# LEDARRAY.net
KiCad netlist of a schematic drawn in EAGLE
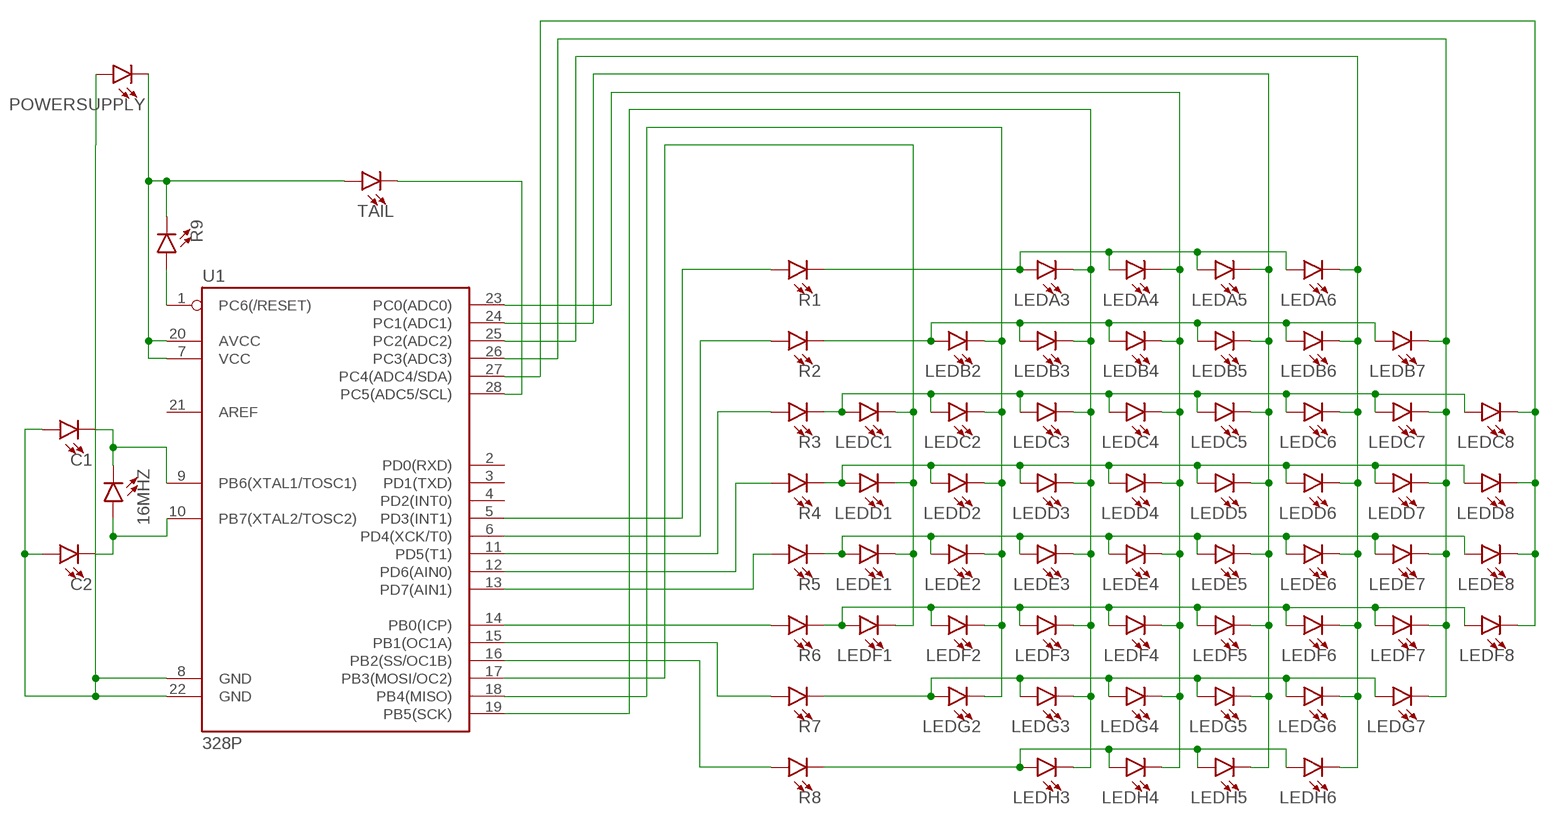
[diagram p0: schematic, sheet 1]

(export (version "E")
  (design (tool "Eeschema 10.0.6"))
  (components
    (comp (ref "16MHZ")
      (value "LED3MM")
      (footprint "eagle-import:LED_3MM")
      (libsource (lib "eagle-import") (part "LED3MM"))
    )
    (comp (ref "C1")
      (value "LED3MM")
      (footprint "eagle-import:LED_3MM")
      (libsource (lib "eagle-import") (part "LED3MM"))
    )
    (comp (ref "C2")
      (value "LED3MM")
      (footprint "eagle-import:LED_3MM")
      (libsource (lib "eagle-import") (part "LED3MM"))
    )
    (comp (ref "LEDA3")
      (value "LED3MM")
      (footprint "eagle-import:LED_3MM")
      (libsource (lib "eagle-import") (part "LED3MM"))
    )
    (comp (ref "LEDA4")
      (value "LED3MM")
      (footprint "eagle-import:LED_3MM")
      (libsource (lib "eagle-import") (part "LED3MM"))
    )
    (comp (ref "LEDA5")
      (value "LED3MM")
      (footprint "eagle-import:LED_3MM")
      (libsource (lib "eagle-import") (part "LED3MM"))
    )
    (comp (ref "LEDA6")
      (value "LED3MM")
      (footprint "eagle-import:LED_3MM")
      (libsource (lib "eagle-import") (part "LED3MM"))
    )
    (comp (ref "LEDB2")
      (value "LED3MM")
      (footprint "eagle-import:LED_3MM")
      (libsource (lib "eagle-import") (part "LED3MM"))
    )
    (comp (ref "LEDB3")
      (value "LED3MM")
      (footprint "eagle-import:LED_3MM")
      (libsource (lib "eagle-import") (part "LED3MM"))
    )
    (comp (ref "LEDB4")
      (value "LED3MM")
      (footprint "eagle-import:LED_3MM")
      (libsource (lib "eagle-import") (part "LED3MM"))
    )
    (comp (ref "LEDB5")
      (value "LED3MM")
      (footprint "eagle-import:LED_3MM")
      (libsource (lib "eagle-import") (part "LED3MM"))
    )
    (comp (ref "LEDB6")
      (value "LED3MM")
      (footprint "eagle-import:LED_3MM")
      (libsource (lib "eagle-import") (part "LED3MM"))
    )
    (comp (ref "LEDB7")
      (value "LED3MM")
      (footprint "eagle-import:LED_3MM")
      (libsource (lib "eagle-import") (part "LED3MM"))
    )
    (comp (ref "LEDC1")
      (value "LED3MM")
      (footprint "eagle-import:LED_3MM")
      (libsource (lib "eagle-import") (part "LED3MM"))
    )
    (comp (ref "LEDC2")
      (value "LED3MM")
      (footprint "eagle-import:LED_3MM")
      (libsource (lib "eagle-import") (part "LED3MM"))
    )
    (comp (ref "LEDC3")
      (value "LED3MM")
      (footprint "eagle-import:LED_3MM")
      (libsource (lib "eagle-import") (part "LED3MM"))
    )
    (comp (ref "LEDC4")
      (value "LED3MM")
      (footprint "eagle-import:LED_3MM")
      (libsource (lib "eagle-import") (part "LED3MM"))
    )
    (comp (ref "LEDC5")
      (value "LED3MM")
      (footprint "eagle-import:LED_3MM")
      (libsource (lib "eagle-import") (part "LED3MM"))
    )
    (comp (ref "LEDC6")
      (value "LED3MM")
      (footprint "eagle-import:LED_3MM")
      (libsource (lib "eagle-import") (part "LED3MM"))
    )
    (comp (ref "LEDC7")
      (value "LED3MM")
      (footprint "eagle-import:LED_3MM")
      (libsource (lib "eagle-import") (part "LED3MM"))
    )
    (comp (ref "LEDC8")
      (value "LED3MM")
      (footprint "eagle-import:LED_3MM")
      (libsource (lib "eagle-import") (part "LED3MM"))
    )
    (comp (ref "LEDD1")
      (value "LED3MM")
      (footprint "eagle-import:LED_3MM")
      (libsource (lib "eagle-import") (part "LED3MM"))
    )
    (comp (ref "LEDD2")
      (value "LED3MM")
      (footprint "eagle-import:LED_3MM")
      (libsource (lib "eagle-import") (part "LED3MM"))
    )
    (comp (ref "LEDD3")
      (value "LED3MM")
      (footprint "eagle-import:LED_3MM")
      (libsource (lib "eagle-import") (part "LED3MM"))
    )
    (comp (ref "LEDD4")
      (value "LED3MM")
      (footprint "eagle-import:LED_3MM")
      (libsource (lib "eagle-import") (part "LED3MM"))
    )
    (comp (ref "LEDD5")
      (value "LED3MM")
      (footprint "eagle-import:LED_3MM")
      (libsource (lib "eagle-import") (part "LED3MM"))
    )
    (comp (ref "LEDD6")
      (value "LED3MM")
      (footprint "eagle-import:LED_3MM")
      (libsource (lib "eagle-import") (part "LED3MM"))
    )
    (comp (ref "LEDD7")
      (value "LED3MM")
      (footprint "eagle-import:LED_3MM")
      (libsource (lib "eagle-import") (part "LED3MM"))
    )
    (comp (ref "LEDD8")
      (value "LED3MM")
      (footprint "eagle-import:LED_3MM")
      (libsource (lib "eagle-import") (part "LED3MM"))
    )
    (comp (ref "LEDE1")
      (value "LED3MM")
      (footprint "eagle-import:LED_3MM")
      (libsource (lib "eagle-import") (part "LED3MM"))
    )
    (comp (ref "LEDE2")
      (value "LED3MM")
      (footprint "eagle-import:LED_3MM")
      (libsource (lib "eagle-import") (part "LED3MM"))
    )
    (comp (ref "LEDE3")
      (value "LED3MM")
      (footprint "eagle-import:LED_3MM")
      (libsource (lib "eagle-import") (part "LED3MM"))
    )
    (comp (ref "LEDE4")
      (value "LED3MM")
      (footprint "eagle-import:LED_3MM")
      (libsource (lib "eagle-import") (part "LED3MM"))
    )
    (comp (ref "LEDE5")
      (value "LED3MM")
      (footprint "eagle-import:LED_3MM")
      (libsource (lib "eagle-import") (part "LED3MM"))
    )
    (comp (ref "LEDE6")
      (value "LED3MM")
      (footprint "eagle-import:LED_3MM")
      (libsource (lib "eagle-import") (part "LED3MM"))
    )
    (comp (ref "LEDE7")
      (value "LED3MM")
      (footprint "eagle-import:LED_3MM")
      (libsource (lib "eagle-import") (part "LED3MM"))
    )
    (comp (ref "LEDE8")
      (value "LED3MM")
      (footprint "eagle-import:LED_3MM")
      (libsource (lib "eagle-import") (part "LED3MM"))
    )
    (comp (ref "LEDF1")
      (value "LED3MM")
      (footprint "eagle-import:LED_3MM")
      (libsource (lib "eagle-import") (part "LED3MM"))
    )
    (comp (ref "LEDF2")
      (value "LED3MM")
      (footprint "eagle-import:LED_3MM")
      (libsource (lib "eagle-import") (part "LED3MM"))
    )
    (comp (ref "LEDF3")
      (value "LED3MM")
      (footprint "eagle-import:LED_3MM")
      (libsource (lib "eagle-import") (part "LED3MM"))
    )
    (comp (ref "LEDF4")
      (value "LED3MM")
      (footprint "eagle-import:LED_3MM")
      (libsource (lib "eagle-import") (part "LED3MM"))
    )
    (comp (ref "LEDF5")
      (value "LED3MM")
      (footprint "eagle-import:LED_3MM")
      (libsource (lib "eagle-import") (part "LED3MM"))
    )
    (comp (ref "LEDF6")
      (value "LED3MM")
      (footprint "eagle-import:LED_3MM")
      (libsource (lib "eagle-import") (part "LED3MM"))
    )
    (comp (ref "LEDF7")
      (value "LED3MM")
      (footprint "eagle-import:LED_3MM")
      (libsource (lib "eagle-import") (part "LED3MM"))
    )
    (comp (ref "LEDF8")
      (value "LED3MM")
      (footprint "eagle-import:LED_3MM")
      (libsource (lib "eagle-import") (part "LED3MM"))
    )
    (comp (ref "LEDG2")
      (value "LED3MM")
      (footprint "eagle-import:LED_3MM")
      (libsource (lib "eagle-import") (part "LED3MM"))
    )
    (comp (ref "LEDG3")
      (value "LED3MM")
      (footprint "eagle-import:LED_3MM")
      (libsource (lib "eagle-import") (part "LED3MM"))
    )
    (comp (ref "LEDG4")
      (value "LED3MM")
      (footprint "eagle-import:LED_3MM")
      (libsource (lib "eagle-import") (part "LED3MM"))
    )
    (comp (ref "LEDG5")
      (value "LED3MM")
      (footprint "eagle-import:LED_3MM")
      (libsource (lib "eagle-import") (part "LED3MM"))
    )
    (comp (ref "LEDG6")
      (value "LED3MM")
      (footprint "eagle-import:LED_3MM")
      (libsource (lib "eagle-import") (part "LED3MM"))
    )
    (comp (ref "LEDG7")
      (value "LED3MM")
      (footprint "eagle-import:LED_3MM")
      (libsource (lib "eagle-import") (part "LED3MM"))
    )
    (comp (ref "LEDH3")
      (value "LED3MM")
      (footprint "eagle-import:LED_3MM")
      (libsource (lib "eagle-import") (part "LED3MM"))
    )
    (comp (ref "LEDH4")
      (value "LED3MM")
      (footprint "eagle-import:LED_3MM")
      (libsource (lib "eagle-import") (part "LED3MM"))
    )
    (comp (ref "LEDH5")
      (value "LED3MM")
      (footprint "eagle-import:LED_3MM")
      (libsource (lib "eagle-import") (part "LED3MM"))
    )
    (comp (ref "LEDH6")
      (value "LED3MM")
      (footprint "eagle-import:LED_3MM")
      (libsource (lib "eagle-import") (part "LED3MM"))
    )
    (comp (ref "POWERSUPPLY")
      (value "LED3MM")
      (footprint "eagle-import:LED_3MM")
      (libsource (lib "eagle-import") (part "LED3MM"))
    )
    (comp (ref "R1")
      (value "LED3MM")
      (footprint "eagle-import:LED_3MM")
      (libsource (lib "eagle-import") (part "LED3MM"))
    )
    (comp (ref "R2")
      (value "LED3MM")
      (footprint "eagle-import:LED_3MM")
      (libsource (lib "eagle-import") (part "LED3MM"))
    )
    (comp (ref "R3")
      (value "LED3MM")
      (footprint "eagle-import:LED_3MM")
      (libsource (lib "eagle-import") (part "LED3MM"))
    )
    (comp (ref "R4")
      (value "LED3MM")
      (footprint "eagle-import:LED_3MM")
      (libsource (lib "eagle-import") (part "LED3MM"))
    )
    (comp (ref "R5")
      (value "LED3MM")
      (footprint "eagle-import:LED_3MM")
      (libsource (lib "eagle-import") (part "LED3MM"))
    )
    (comp (ref "R6")
      (value "LED3MM")
      (footprint "eagle-import:LED_3MM")
      (libsource (lib "eagle-import") (part "LED3MM"))
    )
    (comp (ref "R7")
      (value "LED3MM")
      (footprint "eagle-import:LED_3MM")
      (libsource (lib "eagle-import") (part "LED3MM"))
    )
    (comp (ref "R8")
      (value "LED3MM")
      (footprint "eagle-import:LED_3MM")
      (libsource (lib "eagle-import") (part "LED3MM"))
    )
    (comp (ref "R9")
      (value "LED3MM")
      (footprint "eagle-import:LED_3MM")
      (libsource (lib "eagle-import") (part "LED3MM"))
    )
    (comp (ref "TAIL")
      (value "LED3MM")
      (footprint "eagle-import:LED_3MM")
      (libsource (lib "eagle-import") (part "LED3MM"))
    )
    (comp (ref "U1")
      (value "328P")
      (footprint "eagle-import:DIP28")
      (libsource (lib "eagle-import") (part "ATMEGA328P_PDIP"))
    )
  )
  (nets
    (net (code "1") (name "Net-(16MHZ-C)") (class "Default")
      (node (ref "16MHZ") (pin "K") (pinfunction "C_K") (pintype "passive"))
      (node (ref "C1") (pin "K") (pinfunction "C_K") (pintype "passive"))
      (node (ref "U1") (pin "9") (pinfunction "PB6(XTAL1/TOSC1)_9") (pintype "bidirectional"))
    )
    (net (code "2") (name "Net-(C1-PadA)") (class "Default")
      (node (ref "C1") (pin "A") (pinfunction "A_A") (pintype "passive"))
      (node (ref "C2") (pin "A") (pinfunction "A_A") (pintype "passive"))
      (node (ref "POWERSUPPLY") (pin "A") (pinfunction "A_A") (pintype "passive"))
      (node (ref "U1") (pin "22") (pinfunction "GND_22") (pintype "bidirectional"))
      (node (ref "U1") (pin "8") (pinfunction "GND_8") (pintype "bidirectional"))
    )
    (net (code "3") (name "Net-(C2-C)") (class "Default")
      (node (ref "16MHZ") (pin "A") (pinfunction "A_A") (pintype "passive"))
      (node (ref "C2") (pin "K") (pinfunction "C_K") (pintype "passive"))
      (node (ref "U1") (pin "10") (pinfunction "PB7(XTAL2/TOSC2)_10") (pintype "bidirectional"))
    )
    (net (code "4") (name "Net-(LEDA3-C)") (class "Default")
      (node (ref "LEDA3") (pin "K") (pinfunction "C_K") (pintype "passive"))
      (node (ref "LEDB3") (pin "K") (pinfunction "C_K") (pintype "passive"))
      (node (ref "LEDC3") (pin "K") (pinfunction "C_K") (pintype "passive"))
      (node (ref "LEDD3") (pin "K") (pinfunction "C_K") (pintype "passive"))
      (node (ref "LEDE3") (pin "K") (pinfunction "C_K") (pintype "passive"))
      (node (ref "LEDF3") (pin "K") (pinfunction "C_K") (pintype "passive"))
      (node (ref "LEDG3") (pin "K") (pinfunction "C_K") (pintype "passive"))
      (node (ref "LEDH3") (pin "K") (pinfunction "C_K") (pintype "passive"))
      (node (ref "U1") (pin "19") (pinfunction "PB5(SCK)_19") (pintype "bidirectional"))
    )
    (net (code "5") (name "Net-(LEDA4-C)") (class "Default")
      (node (ref "LEDA4") (pin "K") (pinfunction "C_K") (pintype "passive"))
      (node (ref "LEDB4") (pin "K") (pinfunction "C_K") (pintype "passive"))
      (node (ref "LEDC4") (pin "K") (pinfunction "C_K") (pintype "passive"))
      (node (ref "LEDD4") (pin "K") (pinfunction "C_K") (pintype "passive"))
      (node (ref "LEDE4") (pin "K") (pinfunction "C_K") (pintype "passive"))
      (node (ref "LEDF4") (pin "K") (pinfunction "C_K") (pintype "passive"))
      (node (ref "LEDG4") (pin "K") (pinfunction "C_K") (pintype "passive"))
      (node (ref "LEDH4") (pin "K") (pinfunction "C_K") (pintype "passive"))
      (node (ref "U1") (pin "23") (pinfunction "PC0(ADC0)_23") (pintype "bidirectional"))
    )
    (net (code "6") (name "Net-(LEDA5-C)") (class "Default")
      (node (ref "LEDA5") (pin "K") (pinfunction "C_K") (pintype "passive"))
      (node (ref "LEDB5") (pin "K") (pinfunction "C_K") (pintype "passive"))
      (node (ref "LEDC5") (pin "K") (pinfunction "C_K") (pintype "passive"))
      (node (ref "LEDD5") (pin "K") (pinfunction "C_K") (pintype "passive"))
      (node (ref "LEDE5") (pin "K") (pinfunction "C_K") (pintype "passive"))
      (node (ref "LEDF5") (pin "K") (pinfunction "C_K") (pintype "passive"))
      (node (ref "LEDG5") (pin "K") (pinfunction "C_K") (pintype "passive"))
      (node (ref "LEDH5") (pin "K") (pinfunction "C_K") (pintype "passive"))
      (node (ref "U1") (pin "24") (pinfunction "PC1(ADC1)_24") (pintype "bidirectional"))
    )
    (net (code "7") (name "Net-(LEDA6-C)") (class "Default")
      (node (ref "LEDA6") (pin "K") (pinfunction "C_K") (pintype "passive"))
      (node (ref "LEDB6") (pin "K") (pinfunction "C_K") (pintype "passive"))
      (node (ref "LEDC6") (pin "K") (pinfunction "C_K") (pintype "passive"))
      (node (ref "LEDD6") (pin "K") (pinfunction "C_K") (pintype "passive"))
      (node (ref "LEDE6") (pin "K") (pinfunction "C_K") (pintype "passive"))
      (node (ref "LEDF6") (pin "K") (pinfunction "C_K") (pintype "passive"))
      (node (ref "LEDG6") (pin "K") (pinfunction "C_K") (pintype "passive"))
      (node (ref "LEDH6") (pin "K") (pinfunction "C_K") (pintype "passive"))
      (node (ref "U1") (pin "25") (pinfunction "PC2(ADC2)_25") (pintype "bidirectional"))
    )
    (net (code "8") (name "Net-(LEDB2-C)") (class "Default")
      (node (ref "LEDB2") (pin "K") (pinfunction "C_K") (pintype "passive"))
      (node (ref "LEDC2") (pin "K") (pinfunction "C_K") (pintype "passive"))
      (node (ref "LEDD2") (pin "K") (pinfunction "C_K") (pintype "passive"))
      (node (ref "LEDE2") (pin "K") (pinfunction "C_K") (pintype "passive"))
      (node (ref "LEDF2") (pin "K") (pinfunction "C_K") (pintype "passive"))
      (node (ref "LEDG2") (pin "K") (pinfunction "C_K") (pintype "passive"))
      (node (ref "U1") (pin "18") (pinfunction "PB4(MISO)_18") (pintype "bidirectional"))
    )
    (net (code "9") (name "Net-(LEDB7-C)") (class "Default")
      (node (ref "LEDB7") (pin "K") (pinfunction "C_K") (pintype "passive"))
      (node (ref "LEDC7") (pin "K") (pinfunction "C_K") (pintype "passive"))
      (node (ref "LEDD7") (pin "K") (pinfunction "C_K") (pintype "passive"))
      (node (ref "LEDE7") (pin "K") (pinfunction "C_K") (pintype "passive"))
      (node (ref "LEDF7") (pin "K") (pinfunction "C_K") (pintype "passive"))
      (node (ref "LEDG7") (pin "K") (pinfunction "C_K") (pintype "passive"))
      (node (ref "U1") (pin "26") (pinfunction "PC3(ADC3)_26") (pintype "bidirectional"))
    )
    (net (code "10") (name "Net-(LEDC1-C)") (class "Default")
      (node (ref "LEDC1") (pin "K") (pinfunction "C_K") (pintype "passive"))
      (node (ref "LEDD1") (pin "K") (pinfunction "C_K") (pintype "passive"))
      (node (ref "LEDE1") (pin "K") (pinfunction "C_K") (pintype "passive"))
      (node (ref "LEDF1") (pin "K") (pinfunction "C_K") (pintype "passive"))
      (node (ref "U1") (pin "17") (pinfunction "PB3(MOSI/OC2)_17") (pintype "bidirectional"))
    )
    (net (code "11") (name "Net-(LEDC8-C)") (class "Default")
      (node (ref "LEDC8") (pin "K") (pinfunction "C_K") (pintype "passive"))
      (node (ref "LEDD8") (pin "K") (pinfunction "C_K") (pintype "passive"))
      (node (ref "LEDE8") (pin "K") (pinfunction "C_K") (pintype "passive"))
      (node (ref "LEDF8") (pin "K") (pinfunction "C_K") (pintype "passive"))
      (node (ref "U1") (pin "27") (pinfunction "PC4(ADC4/SDA)_27") (pintype "bidirectional"))
    )
    (net (code "12") (name "Net-(POWERSUPPLY-C)") (class "Default")
      (node (ref "POWERSUPPLY") (pin "K") (pinfunction "C_K") (pintype "passive"))
      (node (ref "R9") (pin "K") (pinfunction "C_K") (pintype "passive"))
      (node (ref "TAIL") (pin "A") (pinfunction "A_A") (pintype "passive"))
      (node (ref "U1") (pin "20") (pinfunction "AVCC_20") (pintype "bidirectional"))
      (node (ref "U1") (pin "7") (pinfunction "VCC_7") (pintype "bidirectional"))
    )
    (net (code "13") (name "Net-(R1-C)") (class "Default")
      (node (ref "LEDA3") (pin "A") (pinfunction "A_A") (pintype "passive"))
      (node (ref "LEDA4") (pin "A") (pinfunction "A_A") (pintype "passive"))
      (node (ref "LEDA5") (pin "A") (pinfunction "A_A") (pintype "passive"))
      (node (ref "LEDA6") (pin "A") (pinfunction "A_A") (pintype "passive"))
      (node (ref "R1") (pin "K") (pinfunction "C_K") (pintype "passive"))
    )
    (net (code "14") (name "Net-(R2-C)") (class "Default")
      (node (ref "LEDB2") (pin "A") (pinfunction "A_A") (pintype "passive"))
      (node (ref "LEDB3") (pin "A") (pinfunction "A_A") (pintype "passive"))
      (node (ref "LEDB4") (pin "A") (pinfunction "A_A") (pintype "passive"))
      (node (ref "LEDB5") (pin "A") (pinfunction "A_A") (pintype "passive"))
      (node (ref "LEDB6") (pin "A") (pinfunction "A_A") (pintype "passive"))
      (node (ref "LEDB7") (pin "A") (pinfunction "A_A") (pintype "passive"))
      (node (ref "R2") (pin "K") (pinfunction "C_K") (pintype "passive"))
    )
    (net (code "15") (name "Net-(R3-C)") (class "Default")
      (node (ref "LEDC1") (pin "A") (pinfunction "A_A") (pintype "passive"))
      (node (ref "LEDC2") (pin "A") (pinfunction "A_A") (pintype "passive"))
      (node (ref "LEDC3") (pin "A") (pinfunction "A_A") (pintype "passive"))
      (node (ref "LEDC4") (pin "A") (pinfunction "A_A") (pintype "passive"))
      (node (ref "LEDC5") (pin "A") (pinfunction "A_A") (pintype "passive"))
      (node (ref "LEDC6") (pin "A") (pinfunction "A_A") (pintype "passive"))
      (node (ref "LEDC7") (pin "A") (pinfunction "A_A") (pintype "passive"))
      (node (ref "LEDC8") (pin "A") (pinfunction "A_A") (pintype "passive"))
      (node (ref "R3") (pin "K") (pinfunction "C_K") (pintype "passive"))
    )
    (net (code "16") (name "Net-(R4-C)") (class "Default")
      (node (ref "LEDD1") (pin "A") (pinfunction "A_A") (pintype "passive"))
      (node (ref "LEDD2") (pin "A") (pinfunction "A_A") (pintype "passive"))
      (node (ref "LEDD3") (pin "A") (pinfunction "A_A") (pintype "passive"))
      (node (ref "LEDD4") (pin "A") (pinfunction "A_A") (pintype "passive"))
      (node (ref "LEDD5") (pin "A") (pinfunction "A_A") (pintype "passive"))
      (node (ref "LEDD6") (pin "A") (pinfunction "A_A") (pintype "passive"))
      (node (ref "LEDD7") (pin "A") (pinfunction "A_A") (pintype "passive"))
      (node (ref "LEDD8") (pin "A") (pinfunction "A_A") (pintype "passive"))
      (node (ref "R4") (pin "K") (pinfunction "C_K") (pintype "passive"))
    )
    (net (code "17") (name "Net-(R5-C)") (class "Default")
      (node (ref "LEDE1") (pin "A") (pinfunction "A_A") (pintype "passive"))
      (node (ref "LEDE2") (pin "A") (pinfunction "A_A") (pintype "passive"))
      (node (ref "LEDE3") (pin "A") (pinfunction "A_A") (pintype "passive"))
      (node (ref "LEDE4") (pin "A") (pinfunction "A_A") (pintype "passive"))
      (node (ref "LEDE5") (pin "A") (pinfunction "A_A") (pintype "passive"))
      (node (ref "LEDE6") (pin "A") (pinfunction "A_A") (pintype "passive"))
      (node (ref "LEDE7") (pin "A") (pinfunction "A_A") (pintype "passive"))
      (node (ref "LEDE8") (pin "A") (pinfunction "A_A") (pintype "passive"))
      (node (ref "R5") (pin "K") (pinfunction "C_K") (pintype "passive"))
    )
    (net (code "18") (name "Net-(R6-C)") (class "Default")
      (node (ref "LEDF1") (pin "A") (pinfunction "A_A") (pintype "passive"))
      (node (ref "LEDF2") (pin "A") (pinfunction "A_A") (pintype "passive"))
      (node (ref "LEDF3") (pin "A") (pinfunction "A_A") (pintype "passive"))
      (node (ref "LEDF4") (pin "A") (pinfunction "A_A") (pintype "passive"))
      (node (ref "LEDF5") (pin "A") (pinfunction "A_A") (pintype "passive"))
      (node (ref "LEDF6") (pin "A") (pinfunction "A_A") (pintype "passive"))
      (node (ref "LEDF7") (pin "A") (pinfunction "A_A") (pintype "passive"))
      (node (ref "LEDF8") (pin "A") (pinfunction "A_A") (pintype "passive"))
      (node (ref "R6") (pin "K") (pinfunction "C_K") (pintype "passive"))
    )
    (net (code "19") (name "Net-(R7-C)") (class "Default")
      (node (ref "LEDG2") (pin "A") (pinfunction "A_A") (pintype "passive"))
      (node (ref "LEDG3") (pin "A") (pinfunction "A_A") (pintype "passive"))
      (node (ref "LEDG4") (pin "A") (pinfunction "A_A") (pintype "passive"))
      (node (ref "LEDG5") (pin "A") (pinfunction "A_A") (pintype "passive"))
      (node (ref "LEDG6") (pin "A") (pinfunction "A_A") (pintype "passive"))
      (node (ref "LEDG7") (pin "A") (pinfunction "A_A") (pintype "passive"))
      (node (ref "R7") (pin "K") (pinfunction "C_K") (pintype "passive"))
    )
    (net (code "20") (name "Net-(R8-C)") (class "Default")
      (node (ref "LEDH3") (pin "A") (pinfunction "A_A") (pintype "passive"))
      (node (ref "LEDH4") (pin "A") (pinfunction "A_A") (pintype "passive"))
      (node (ref "LEDH5") (pin "A") (pinfunction "A_A") (pintype "passive"))
      (node (ref "LEDH6") (pin "A") (pinfunction "A_A") (pintype "passive"))
      (node (ref "R8") (pin "K") (pinfunction "C_K") (pintype "passive"))
    )
    (net (code "21") (name "Net-(TAIL-C)") (class "Default")
      (node (ref "TAIL") (pin "K") (pinfunction "C_K") (pintype "passive"))
      (node (ref "U1") (pin "28") (pinfunction "PC5(ADC5/SCL)_28") (pintype "bidirectional"))
    )
    (net (code "22") (name "Net-(U1-PB0(ICP))") (class "Default")
      (node (ref "R6") (pin "A") (pinfunction "A_A") (pintype "passive"))
      (node (ref "U1") (pin "14") (pinfunction "PB0(ICP)_14") (pintype "bidirectional"))
    )
    (net (code "23") (name "Net-(U1-PB1(OC1A))") (class "Default")
      (node (ref "R7") (pin "A") (pinfunction "A_A") (pintype "passive"))
      (node (ref "U1") (pin "15") (pinfunction "PB1(OC1A)_15") (pintype "bidirectional"))
    )
    (net (code "24") (name "Net-(U1-PB2(SS{slash}OC1B))") (class "Default")
      (node (ref "R8") (pin "A") (pinfunction "A_A") (pintype "passive"))
      (node (ref "U1") (pin "16") (pinfunction "PB2(SS/OC1B)_16") (pintype "bidirectional"))
    )
    (net (code "25") (name "Net-(U1-PC6({slash}RESET))") (class "Default")
      (node (ref "R9") (pin "A") (pinfunction "A_A") (pintype "passive"))
      (node (ref "U1") (pin "1") (pinfunction "PC6(/RESET)_1") (pintype "bidirectional"))
    )
    (net (code "26") (name "Net-(U1-PD3(INT1))") (class "Default")
      (node (ref "R1") (pin "A") (pinfunction "A_A") (pintype "passive"))
      (node (ref "U1") (pin "5") (pinfunction "PD3(INT1)_5") (pintype "bidirectional"))
    )
    (net (code "27") (name "Net-(U1-PD4(XCK{slash}T0))") (class "Default")
      (node (ref "R2") (pin "A") (pinfunction "A_A") (pintype "passive"))
      (node (ref "U1") (pin "6") (pinfunction "PD4(XCK/T0)_6") (pintype "bidirectional"))
    )
    (net (code "28") (name "Net-(U1-PD5(T1))") (class "Default")
      (node (ref "R3") (pin "A") (pinfunction "A_A") (pintype "passive"))
      (node (ref "U1") (pin "11") (pinfunction "PD5(T1)_11") (pintype "bidirectional"))
    )
    (net (code "29") (name "Net-(U1-PD6(AIN0))") (class "Default")
      (node (ref "R4") (pin "A") (pinfunction "A_A") (pintype "passive"))
      (node (ref "U1") (pin "12") (pinfunction "PD6(AIN0)_12") (pintype "bidirectional"))
    )
    (net (code "30") (name "Net-(U1-PD7(AIN1))") (class "Default")
      (node (ref "R5") (pin "A") (pinfunction "A_A") (pintype "passive"))
      (node (ref "U1") (pin "13") (pinfunction "PD7(AIN1)_13") (pintype "bidirectional"))
    )
    (net (code "31") (name "unconnected-(U1-AREF-Pad21)") (class "Default")
      (node (ref "U1") (pin "21") (pinfunction "AREF_21") (pintype "bidirectional"))
    )
    (net (code "32") (name "unconnected-(U1-PD0(RXD)-Pad2)") (class "Default")
      (node (ref "U1") (pin "2") (pinfunction "PD0(RXD)_2") (pintype "bidirectional"))
    )
    (net (code "33") (name "unconnected-(U1-PD1(TXD)-Pad3)") (class "Default")
      (node (ref "U1") (pin "3") (pinfunction "PD1(TXD)_3") (pintype "bidirectional"))
    )
    (net (code "34") (name "unconnected-(U1-PD2(INT0)-Pad4)") (class "Default")
      (node (ref "U1") (pin "4") (pinfunction "PD2(INT0)_4") (pintype "bidirectional"))
    )
  )
)
